# H03R00-J.net
KiCad netlist of a schematic drawn in EAGLE
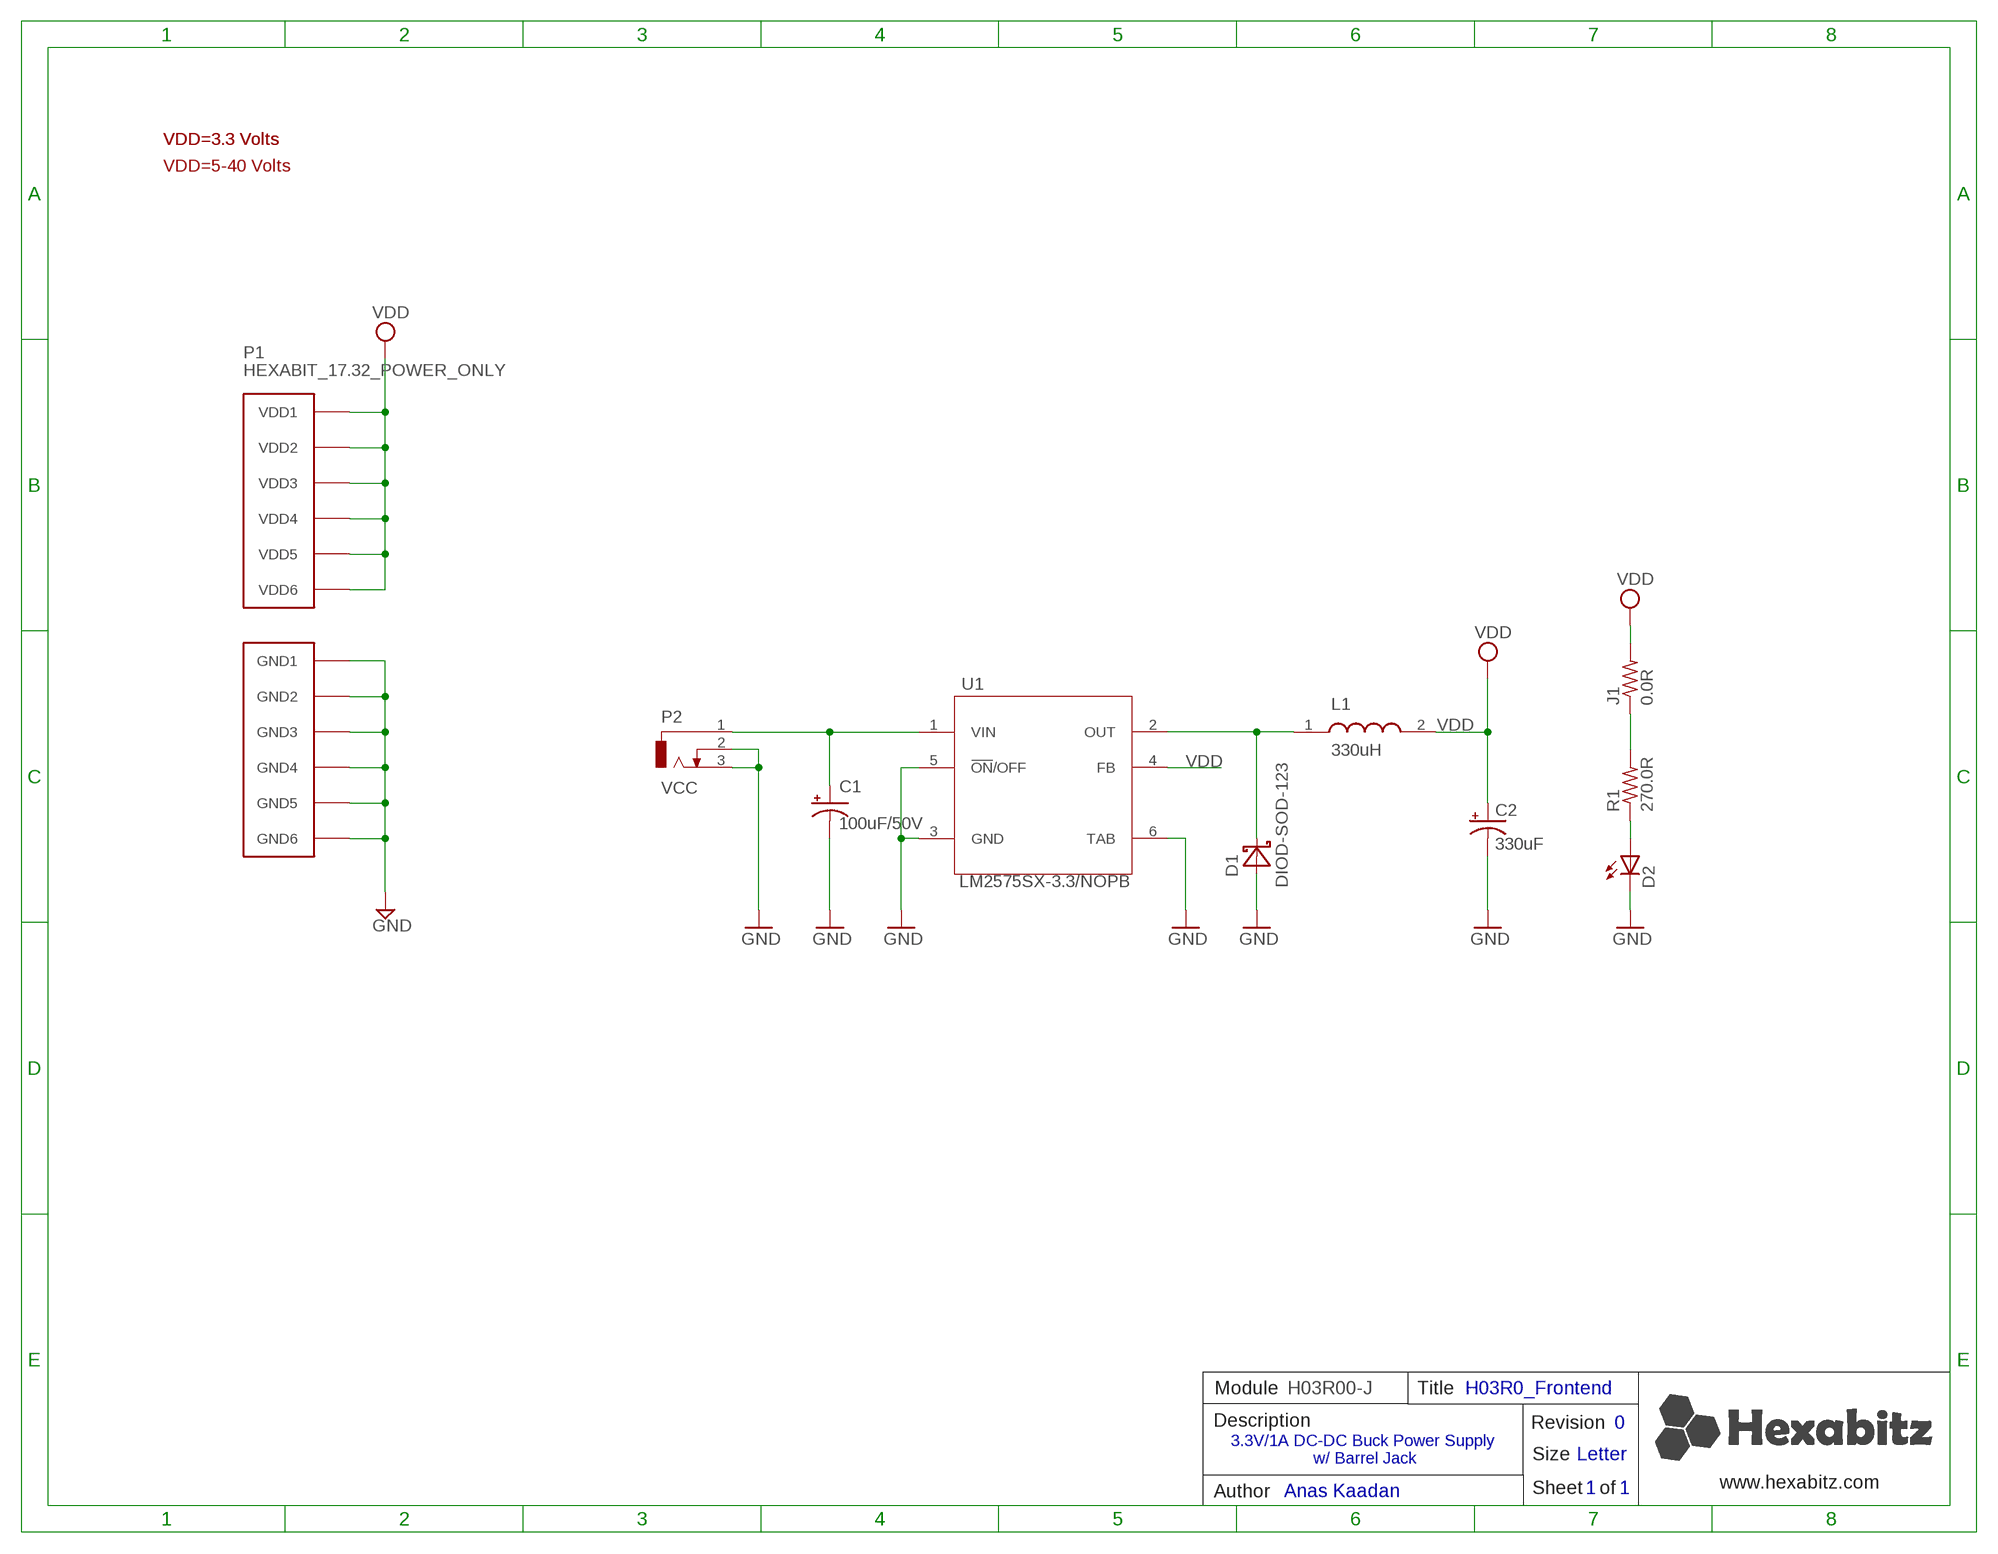
[diagram p0: schematic, sheet 1]

(export (version "E")
  (design (tool "Eeschema 10.0.6"))
  (components
    (comp (ref "C1")
      (value "100uF/50V")
      (footprint "eagle-import:E3,5-8")
      (fields
        (field (name "CAPACITANCE") "100F")
        (field (name "CPACITANCE_RATING") "±20%")
        (field (name "MFN") "Nichicon")
        (field (name "MPN") "UVR1H101MPD1TD")
        (field (name "OCTOPART_ID") "913e58b97f3b4ef9")
        (field (name "OCTOPART_URL") "http://octopart.com/uvr1h101mpd1td-nichicon-9292643")
        (field (name "VOLTAGE_RATING_DC") "50.0 V")
      )
      (libsource (lib "eagle-import") (part "CPOL-US"))
    )
    (comp (ref "C2")
      (value "330uF")
      (footprint "eagle-import:CAPPM7343X200N")
      (fields
        (field (name "MANUFACTURER_PART_NUMBER") "6TPC330MA")
        (field (name "MOUSER_PART_NUMBER") "667-6TPC330MA")
        (field (name "RS_PART_NUMBER") "1666900")
      )
      (libsource (lib "eagle-import") (part "AVX-E"))
    )
    (comp (ref "D1")
      (value "DIOD-SOD-123")
      (footprint "eagle-import:SOD123")
      (fields
        (field (name "CAPACITANCE") "1.1e-10 F")
        (field (name "CURRENT_RATING") "1.0 A")
        (field (name "MFN") "diodes")
        (field (name "MPN") "1N5819HW-7-F")
        (field (name "OCTOPART_ID") "e83e2130232537f9")
        (field (name "OCTOPART_URL") "https://octopart.com/1n5819hw-7-f-diodes+inc.-323197")
        (field (name "VOLTAGE_RATING_DC") "40.0 V")
      )
      (libsource (lib "eagle-import") (part "DIOD-SOD-123"))
    )
    (comp (ref "D2")
      (value "VLMS1300-GS08")
      (footprint "eagle-import:VLMS1300-GS08")
      (fields
        (field (name "MFN") "Vishay")
        (field (name "MPN") "VLMTG1300-GS08")
        (field (name "OCTOPART_URL") "http://octopart.com/vlmtg1300-gs08-vishay-21709202")
      )
      (libsource (lib "eagle-import") (part "VLMS1300-GS08"))
    )
    (comp (ref "J1")
      (value "0.0R")
      (footprint "eagle-import:R-0603")
      (fields
        (field (name "MFN") "Yageo")
        (field (name "MPN") "RC0603JR-070RL")
        (field (name "OCTOPART_URL") "https://octopart.com/crcw06030000z0eahp-vishay-44320230")
        (field (name "RESISTANCE") "0.0 Ω")
      )
      (libsource (lib "eagle-import") (part "R-0603"))
    )
    (comp (ref "L1")
      (value "330uH")
      (footprint "eagle-import:SRR1280-150M")
      (fields
        (field (name "MANUFACTURER_PART_NUMBER") "SRR1280-331K")
        (field (name "MOUSER_PART_NUMBER") "652-SRR1280-331K")
        (field (name "RS_PART_NUMBER") "1728540")
      )
      (libsource (lib "eagle-import") (part "SRR1280-331K"))
    )
    (comp (ref "P1")
      (value "HEXABIT_17.32_POWER_ONLY")
      (footprint "eagle-import:HEXABIT_17.32_POWER_ONLY")
      (libsource (lib "eagle-import") (part "HEXABIT_?_POWER_ONLY17.32"))
    )
    (comp (ref "P2")
      (value "VCC")
      (footprint "eagle-import:DCJ0202")
      (fields (field (name "MF") "CUI") (field (name "MPN") "PJ-202A"))
      (libsource (lib "eagle-import") (part "DCJ0202"))
    )
    (comp (ref "R1")
      (value "270.0R")
      (footprint "eagle-import:R-0603")
      (fields
        (field (name "MFN") "Yageo")
        (field (name "MPN") "RC0603FR-07270RL")
        (field (name "OCTOPART_URL") "https://octopart.com/crcw0603270rjnea-vishay-39784736")
        (field (name "RESISTANCE") "270.0 Ω")
        (field (name "TOLERANCE") "±5%")
      )
      (libsource (lib "eagle-import") (part "R-0603"))
    )
    (comp (ref "U1")
      (value "LM2575SX-3.3/NOPB")
      (footprint "eagle-import:TO170P1435X457-6N")
      (fields
        (field (name "DIGI-KEY_PART_NUMBER") "LM2575SX-3.3/NOPBCT-ND")
        (field (name "MF") "Texas Instruments")
      )
      (libsource (lib "eagle-import") (part "LM2575SX-3.3/NOPB"))
    )
  )
  (nets
    (net (code "1") (name "GND") (class "Default")
      (node (ref "C1") (pin "-") (pinfunction "-_-") (pintype "passive"))
      (node (ref "C2") (pin "2") (pinfunction "-_2") (pintype "passive"))
      (node (ref "D1") (pin "1") (pinfunction "A_1") (pintype "passive"))
      (node (ref "D2") (pin "C") (pinfunction "C_C") (pintype "passive"))
      (node (ref "P1") (pin "PAD_PD10") (pinfunction "GND4_PAD_PD10") (pintype "power_in"))
      (node (ref "P1") (pin "PAD_PD11") (pinfunction "GND5_PAD_PD11") (pintype "power_in"))
      (node (ref "P1") (pin "PAD_PD12") (pinfunction "GND6_PAD_PD12") (pintype "power_in"))
      (node (ref "P1") (pin "PAD_PD7") (pinfunction "GND1_PAD_PD7") (pintype "power_in"))
      (node (ref "P1") (pin "PAD_PD8") (pinfunction "GND2_PAD_PD8") (pintype "power_in"))
      (node (ref "P1") (pin "PAD_PD9") (pinfunction "GND3_PAD_PD9") (pintype "power_in"))
      (node (ref "P2") (pin "2") (pinfunction "2_2") (pintype "passive"))
      (node (ref "P2") (pin "3") (pinfunction "3_3") (pintype "passive"))
      (node (ref "U1") (pin "3") (pinfunction "GND_3") (pintype "passive"))
      (node (ref "U1") (pin "5") (pinfunction "ON/OFF_5") (pintype "input"))
      (node (ref "U1") (pin "6") (pinfunction "TAB_6") (pintype "passive"))
    )
    (net (code "2") (name "Net-(D1-C)") (class "Default")
      (node (ref "D1") (pin "2") (pinfunction "C_2") (pintype "passive"))
      (node (ref "L1") (pin "1") (pinfunction "1_1") (pintype "bidirectional"))
      (node (ref "U1") (pin "2") (pinfunction "OUT_2") (pintype "output"))
    )
    (net (code "3") (name "Net-(D2-PadA)") (class "Default")
      (node (ref "D2") (pin "A") (pinfunction "A_A") (pintype "passive"))
      (node (ref "R1") (pin "1") (pinfunction "1_1") (pintype "passive"))
    )
    (net (code "4") (name "Net-(J1-Pad1)") (class "Default")
      (node (ref "J1") (pin "1") (pinfunction "1_1") (pintype "passive"))
      (node (ref "R1") (pin "2") (pinfunction "2_2") (pintype "passive"))
    )
    (net (code "5") (name "Net-(U1-VIN)") (class "Default")
      (node (ref "C1") (pin "+") (pinfunction "+_+") (pintype "passive"))
      (node (ref "P2") (pin "1") (pinfunction "1_1") (pintype "passive"))
      (node (ref "U1") (pin "1") (pinfunction "VIN_1") (pintype "power_in"))
    )
    (net (code "6") (name "VDD") (class "Default")
      (node (ref "C2") (pin "1") (pinfunction "+_1") (pintype "passive"))
      (node (ref "J1") (pin "2") (pinfunction "2_2") (pintype "passive"))
      (node (ref "L1") (pin "2") (pinfunction "2_2") (pintype "bidirectional"))
      (node (ref "P1") (pin "PAD_PU10") (pinfunction "VDD4_PAD_PU10") (pintype "power_in"))
      (node (ref "P1") (pin "PAD_PU11") (pinfunction "VDD5_PAD_PU11") (pintype "power_in"))
      (node (ref "P1") (pin "PAD_PU12") (pinfunction "VDD6_PAD_PU12") (pintype "power_in"))
      (node (ref "P1") (pin "PAD_PU7") (pinfunction "VDD1_PAD_PU7") (pintype "power_in"))
      (node (ref "P1") (pin "PAD_PU8") (pinfunction "VDD2_PAD_PU8") (pintype "power_in"))
      (node (ref "P1") (pin "PAD_PU9") (pinfunction "VDD3_PAD_PU9") (pintype "power_in"))
      (node (ref "U1") (pin "4") (pinfunction "FB_4") (pintype "input"))
    )
  )
)
